# Pg13_FPGA_Connectors.net
KiCad netlist of a schematic drawn in Altium Designer
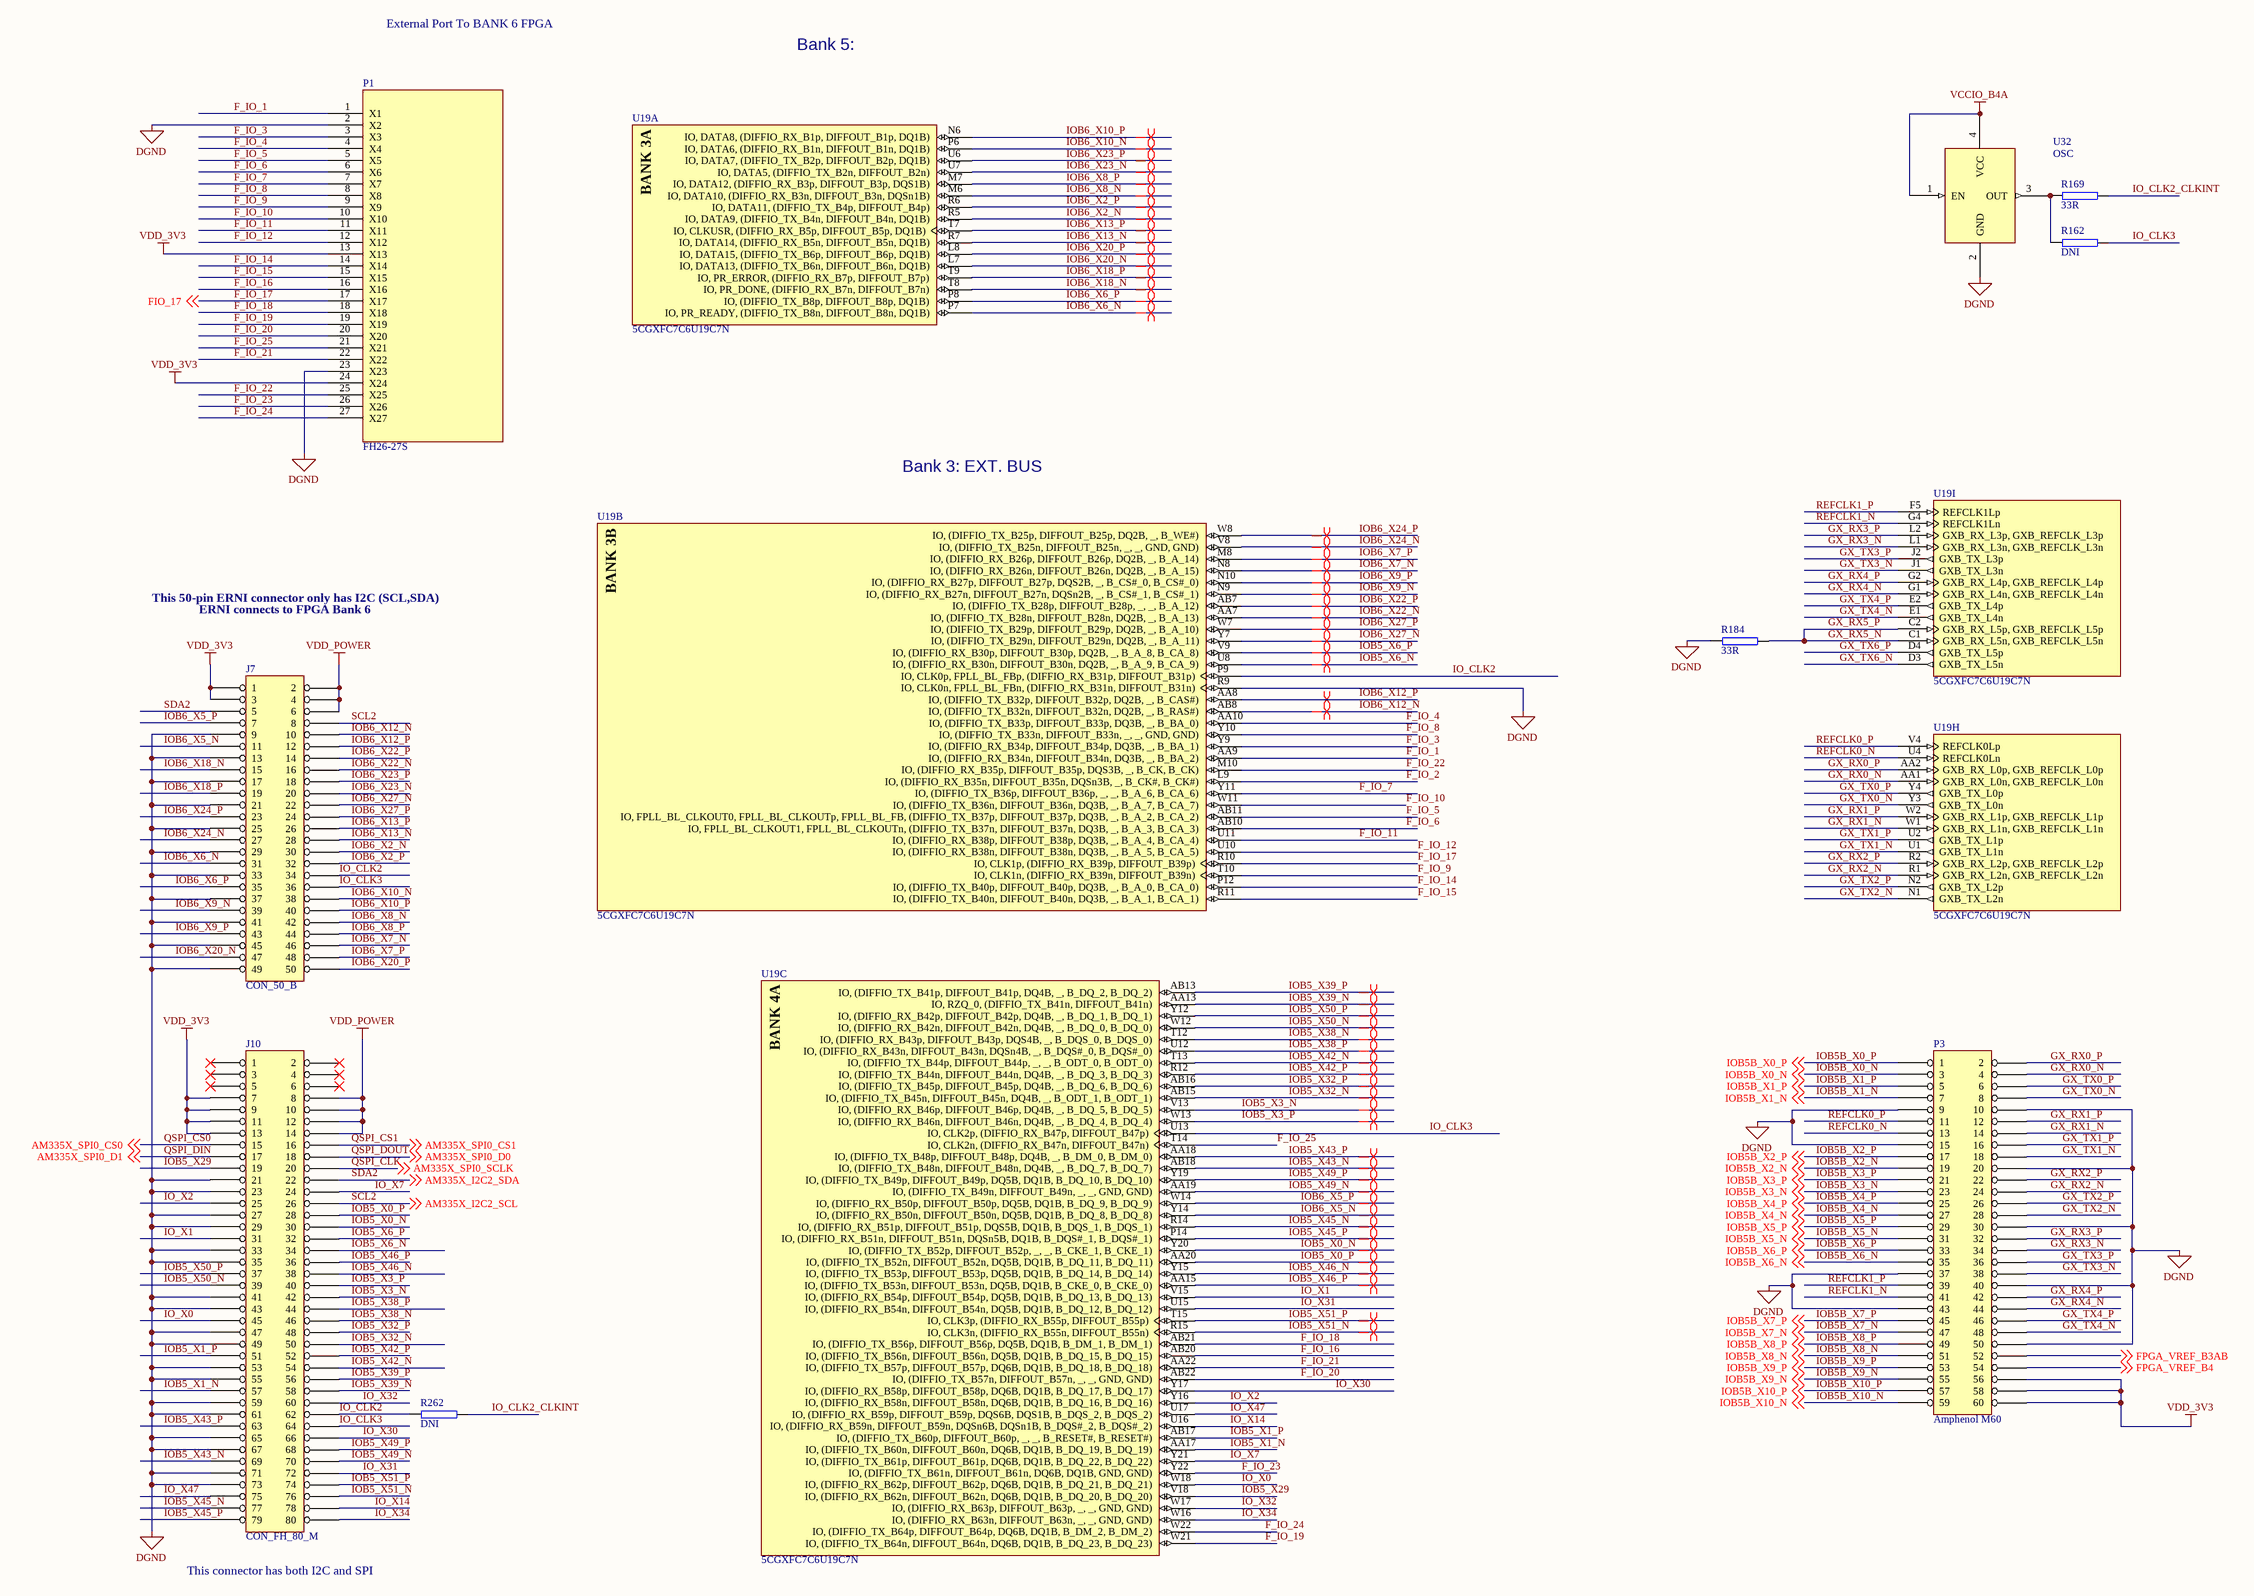
[diagram p0: Pg13_FPGA_Connectors.SchDoc]

(export (version "E")
  (design (tool "Eeschema 10.0.6"))
  (components
    (comp (ref "J7")
      (value "CON_50_B")
      (footprint "CON_50_B")
      (description "HEADER 25X2")
      (libsource (lib "Fireflash_B") (part "CON_50_B"))
    )
    (comp (ref "J10")
      (value "CON_FH_80_M")
      (footprint "CON_FH_80_M")
      (description "AMPHENOL FH")
      (libsource (lib "Fireflash_B") (part "CON_FH_80_M"))
    )
    (comp (ref "P1")
      (value "FH26-27S")
      (footprint "FH26-27S")
      (description "Flexible PCB connector")
      (libsource (lib "Fireflash_B") (part "FH26-27S"))
    )
    (comp (ref "P3")
      (value "Amphenol M60")
      (footprint "CON60_M")
      (description "Header vertical 60 M")
      (libsource (lib "AddtoMini_revC") (part "CON60_FH_M"))
    )
    (comp (ref "R162")
      (value "DNI")
      (footprint "sc0402")
      (description "Resistor")
      (libsource (lib "Ibis4") (part "RES"))
    )
    (comp (ref "R169")
      (value "33R")
      (footprint "sc0402")
      (description "Resistor")
      (libsource (lib "Ibis4") (part "RES"))
    )
    (comp (ref "R184")
      (value "33R")
      (footprint "sc0402")
      (description "Resistor")
      (libsource (lib "Ibis4") (part "RES"))
    )
    (comp (ref "R262")
      (value "DNI")
      (footprint "sc0402")
      (description "Resistor")
      (libsource (lib "Ibis4") (part "RES"))
    )
    (comp (ref "U19")
      (value "5CGXFC7C6U19C7N")
      (footprint "ALTR-UBGA484_A-190")
      (fields (field (name "MANUFACTURER") "Altera"))
      (libsource (lib "Altera Cyclone V") (part "5CGXFC7C6U19C7N"))
    )
    (comp (ref "U32")
      (value "OSC")
      (footprint "Osc 3.2x2.5")
      (description "XTAL OSCILLATOR MODULE")
      (libsource (lib "Fireflash_B") (part "OSC"))
    )
  )
  (nets
    (net (code "1") (name "/F_IO_1") (class "Default")
      (node (ref "P1") (pin "1") (pinfunction "X1_1") (pintype "passive"))
      (node (ref "U19") (pin "AA9") (pinfunction "IO,_(DIFFIO_RX_B34n,_DIFFOUT_B34n,_DQ3B,__,_B_BA_2)_AA9") (pintype "bidirectional"))
    )
    (net (code "2") (name "/F_IO_2") (class "Default")
      (node (ref "U19") (pin "L9") (pinfunction "IO,_(DIFFIO_RX_B35n,_DIFFOUT_B35n,_DQSn3B,__,_B_CK#,_B_CK#)_L9") (pintype "bidirectional"))
    )
    (net (code "3") (name "/F_IO_3") (class "Default")
      (node (ref "P1") (pin "3") (pinfunction "X3_3") (pintype "passive"))
      (node (ref "U19") (pin "Y9") (pinfunction "IO,_(DIFFIO_RX_B34p,_DIFFOUT_B34p,_DQ3B,__,_B_BA_1)_Y9") (pintype "bidirectional"))
    )
    (net (code "4") (name "/F_IO_4") (class "Default")
      (node (ref "P1") (pin "4") (pinfunction "X4_4") (pintype "passive"))
      (node (ref "U19") (pin "AA10") (pinfunction "IO,_(DIFFIO_TX_B33p,_DIFFOUT_B33p,_DQ3B,__,_B_BA_0)_AA10") (pintype "bidirectional"))
    )
    (net (code "5") (name "/F_IO_5") (class "Default")
      (node (ref "P1") (pin "5") (pinfunction "X5_5") (pintype "passive"))
      (node (ref "U19") (pin "AB11") (pinfunction "IO,_FPLL_BL_CLKOUT0,_FPLL_BL_CLKOUTp,_FPLL_BL_FB,_(DIFFIO_TX_B37p,_DIFFOUT_B37p,_DQ3B,__,_B_A_2,_B_CA_2)_AB11") (pintype "bidirectional"))
    )
    (net (code "6") (name "/F_IO_6") (class "Default")
      (node (ref "P1") (pin "6") (pinfunction "X6_6") (pintype "passive"))
      (node (ref "U19") (pin "AB10") (pinfunction "IO,_FPLL_BL_CLKOUT1,_FPLL_BL_CLKOUTn,_(DIFFIO_TX_B37n,_DIFFOUT_B37n,_DQ3B,__,_B_A_3,_B_CA_3)_AB10") (pintype "bidirectional"))
    )
    (net (code "7") (name "/F_IO_7") (class "Default")
      (node (ref "P1") (pin "7") (pinfunction "X7_7") (pintype "passive"))
      (node (ref "U19") (pin "Y11") (pinfunction "IO,_(DIFFIO_TX_B36p,_DIFFOUT_B36p,__,__,_B_A_6,_B_CA_6)_Y11") (pintype "bidirectional"))
    )
    (net (code "8") (name "/F_IO_8") (class "Default")
      (node (ref "P1") (pin "8") (pinfunction "X8_8") (pintype "passive"))
      (node (ref "U19") (pin "Y10") (pinfunction "IO,_(DIFFIO_TX_B33n,_DIFFOUT_B33n,__,__,_GND,_GND)_Y10") (pintype "bidirectional"))
    )
    (net (code "9") (name "/F_IO_9") (class "Default")
      (node (ref "P1") (pin "9") (pinfunction "X9_9") (pintype "passive"))
      (node (ref "U19") (pin "T10") (pinfunction "IO,_CLK1n,_(DIFFIO_RX_B39n,_DIFFOUT_B39n)_T10") (pintype "bidirectional"))
    )
    (net (code "10") (name "/F_IO_10") (class "Default")
      (node (ref "P1") (pin "10") (pinfunction "X10_10") (pintype "passive"))
      (node (ref "U19") (pin "W11") (pinfunction "IO,_(DIFFIO_TX_B36n,_DIFFOUT_B36n,_DQ3B,__,_B_A_7,_B_CA_7)_W11") (pintype "bidirectional"))
    )
    (net (code "11") (name "/F_IO_11") (class "Default")
      (node (ref "P1") (pin "11") (pinfunction "X11_11") (pintype "passive"))
      (node (ref "U19") (pin "U11") (pinfunction "IO,_(DIFFIO_RX_B38p,_DIFFOUT_B38p,_DQ3B,__,_B_A_4,_B_CA_4)_U11") (pintype "bidirectional"))
    )
    (net (code "12") (name "/F_IO_12") (class "Default")
      (node (ref "P1") (pin "12") (pinfunction "X12_12") (pintype "passive"))
      (node (ref "U19") (pin "U10") (pinfunction "IO,_(DIFFIO_RX_B38n,_DIFFOUT_B38n,_DQ3B,__,_B_A_5,_B_CA_5)_U10") (pintype "bidirectional"))
    )
    (net (code "13") (name "/F_IO_14") (class "Default")
      (node (ref "P1") (pin "14") (pinfunction "X14_14") (pintype "passive"))
      (node (ref "U19") (pin "P12") (pinfunction "IO,_(DIFFIO_TX_B40p,_DIFFOUT_B40p,_DQ3B,__,_B_A_0,_B_CA_0)_P12") (pintype "bidirectional"))
    )
    (net (code "14") (name "/F_IO_15") (class "Default")
      (node (ref "P1") (pin "15") (pinfunction "X15_15") (pintype "passive"))
      (node (ref "U19") (pin "R11") (pinfunction "IO,_(DIFFIO_TX_B40n,_DIFFOUT_B40n,_DQ3B,__,_B_A_1,_B_CA_1)_R11") (pintype "bidirectional"))
    )
    (net (code "15") (name "/F_IO_16") (class "Default")
      (node (ref "P1") (pin "16") (pinfunction "X16_16") (pintype "passive"))
      (node (ref "U19") (pin "AB20") (pinfunction "IO,_(DIFFIO_TX_B56n,_DIFFOUT_B56n,_DQ5B,_DQ1B,_B_DQ_15,_B_DQ_15)_AB20") (pintype "bidirectional"))
    )
    (net (code "16") (name "/F_IO_18") (class "Default")
      (node (ref "P1") (pin "18") (pinfunction "X18_18") (pintype "passive"))
      (node (ref "U19") (pin "AB21") (pinfunction "IO,_(DIFFIO_TX_B56p,_DIFFOUT_B56p,_DQ5B,_DQ1B,_B_DM_1,_B_DM_1)_AB21") (pintype "bidirectional"))
    )
    (net (code "17") (name "/F_IO_19") (class "Default")
      (node (ref "P1") (pin "19") (pinfunction "X19_19") (pintype "passive"))
      (node (ref "U19") (pin "W21") (pinfunction "IO,_(DIFFIO_TX_B64n,_DIFFOUT_B64n,_DQ6B,_DQ1B,_B_DQ_23,_B_DQ_23)_W21") (pintype "bidirectional"))
    )
    (net (code "18") (name "/F_IO_20") (class "Default")
      (node (ref "P1") (pin "20") (pinfunction "X20_20") (pintype "passive"))
      (node (ref "U19") (pin "AB22") (pinfunction "IO,_(DIFFIO_TX_B57n,_DIFFOUT_B57n,__,__,_GND,_GND)_AB22") (pintype "bidirectional"))
    )
    (net (code "19") (name "/F_IO_21") (class "Default")
      (node (ref "P1") (pin "22") (pinfunction "X22_22") (pintype "passive"))
      (node (ref "U19") (pin "AA22") (pinfunction "IO,_(DIFFIO_TX_B57p,_DIFFOUT_B57p,_DQ6B,_DQ1B,_B_DQ_18,_B_DQ_18)_AA22") (pintype "bidirectional"))
    )
    (net (code "20") (name "/F_IO_22") (class "Default")
      (node (ref "P1") (pin "25") (pinfunction "X25_25") (pintype "passive"))
      (node (ref "U19") (pin "M10") (pinfunction "IO,_(DIFFIO_RX_B35p,_DIFFOUT_B35p,_DQS3B,__,_B_CK,_B_CK)_M10") (pintype "bidirectional"))
    )
    (net (code "21") (name "/F_IO_23") (class "Default")
      (node (ref "P1") (pin "26") (pinfunction "X26_26") (pintype "passive"))
      (node (ref "U19") (pin "Y22") (pinfunction "IO,_(DIFFIO_TX_B61n,_DIFFOUT_B61n,_DQ6B,_DQ1B,_GND,_GND)_Y22") (pintype "bidirectional"))
    )
    (net (code "22") (name "/F_IO_24") (class "Default")
      (node (ref "P1") (pin "27") (pinfunction "X27_27") (pintype "passive"))
      (node (ref "U19") (pin "W22") (pinfunction "IO,_(DIFFIO_TX_B64p,_DIFFOUT_B64p,_DQ6B,_DQ1B,_B_DM_2,_B_DM_2)_W22") (pintype "bidirectional"))
    )
    (net (code "23") (name "/F_IO_25") (class "Default")
      (node (ref "P1") (pin "21") (pinfunction "X21_21") (pintype "passive"))
      (node (ref "U19") (pin "T14") (pinfunction "IO,_CLK2n,_(DIFFIO_RX_B47n,_DIFFOUT_B47n)_T14") (pintype "bidirectional"))
    )
    (net (code "24") (name "/GX_RX0_N") (class "Default")
      (node (ref "P3") (pin "4") (pinfunction "4_4") (pintype "passive"))
      (node (ref "U19") (pin "AA1") (pinfunction "GXB_RX_L0n,_GXB_REFCLK_L0n_AA1") (pintype "input"))
    )
    (net (code "25") (name "/GX_RX0_P") (class "Default")
      (node (ref "P3") (pin "2") (pinfunction "2_2") (pintype "passive"))
      (node (ref "U19") (pin "AA2") (pinfunction "GXB_RX_L0p,_GXB_REFCLK_L0p_AA2") (pintype "input"))
    )
    (net (code "26") (name "/GX_RX1_N") (class "Default")
      (node (ref "P3") (pin "14") (pinfunction "14_14") (pintype "passive"))
      (node (ref "U19") (pin "W1") (pinfunction "GXB_RX_L1n,_GXB_REFCLK_L1n_W1") (pintype "input"))
    )
    (net (code "27") (name "/GX_RX1_P") (class "Default")
      (node (ref "P3") (pin "12") (pinfunction "12_12") (pintype "passive"))
      (node (ref "U19") (pin "W2") (pinfunction "GXB_RX_L1p,_GXB_REFCLK_L1p_W2") (pintype "input"))
    )
    (net (code "28") (name "/GX_RX2_N") (class "Default")
      (node (ref "P3") (pin "24") (pinfunction "24_24") (pintype "passive"))
      (node (ref "U19") (pin "R1") (pinfunction "GXB_RX_L2n,_GXB_REFCLK_L2n_R1") (pintype "input"))
    )
    (net (code "29") (name "/GX_RX2_P") (class "Default")
      (node (ref "P3") (pin "22") (pinfunction "22_22") (pintype "passive"))
      (node (ref "U19") (pin "R2") (pinfunction "GXB_RX_L2p,_GXB_REFCLK_L2p_R2") (pintype "input"))
    )
    (net (code "30") (name "/GX_RX3_N") (class "Default")
      (node (ref "P3") (pin "34") (pinfunction "34_34") (pintype "passive"))
      (node (ref "U19") (pin "L1") (pinfunction "GXB_RX_L3n,_GXB_REFCLK_L3n_L1") (pintype "input"))
    )
    (net (code "31") (name "/GX_RX3_P") (class "Default")
      (node (ref "P3") (pin "32") (pinfunction "32_32") (pintype "passive"))
      (node (ref "U19") (pin "L2") (pinfunction "GXB_RX_L3p,_GXB_REFCLK_L3p_L2") (pintype "input"))
    )
    (net (code "32") (name "/GX_RX4_N") (class "Default")
      (node (ref "P3") (pin "44") (pinfunction "44_44") (pintype "passive"))
      (node (ref "U19") (pin "G1") (pinfunction "GXB_RX_L4n,_GXB_REFCLK_L4n_G1") (pintype "input"))
    )
    (net (code "33") (name "/GX_RX4_P") (class "Default")
      (node (ref "P3") (pin "42") (pinfunction "42_42") (pintype "passive"))
      (node (ref "U19") (pin "G2") (pinfunction "GXB_RX_L4p,_GXB_REFCLK_L4p_G2") (pintype "input"))
    )
    (net (code "34") (name "/GX_RX5_N") (class "Default")
      (node (ref "R184") (pin "2") (pintype "passive"))
      (node (ref "U19") (pin "C1") (pinfunction "GXB_RX_L5n,_GXB_REFCLK_L5n_C1") (pintype "input"))
      (node (ref "U19") (pin "C2") (pinfunction "GXB_RX_L5p,_GXB_REFCLK_L5p_C2") (pintype "input"))
    )
    (net (code "35") (name "/GX_TX0_N") (class "Default")
      (node (ref "P3") (pin "8") (pinfunction "8_8") (pintype "passive"))
      (node (ref "U19") (pin "Y3") (pinfunction "GXB_TX_L0n_Y3") (pintype "output"))
    )
    (net (code "36") (name "/GX_TX0_P") (class "Default")
      (node (ref "P3") (pin "6") (pinfunction "6_6") (pintype "passive"))
      (node (ref "U19") (pin "Y4") (pinfunction "GXB_TX_L0p_Y4") (pintype "output"))
    )
    (net (code "37") (name "/GX_TX1_N") (class "Default")
      (node (ref "P3") (pin "18") (pinfunction "18_18") (pintype "passive"))
      (node (ref "U19") (pin "U1") (pinfunction "GXB_TX_L1n_U1") (pintype "output"))
    )
    (net (code "38") (name "/GX_TX1_P") (class "Default")
      (node (ref "P3") (pin "16") (pinfunction "16_16") (pintype "passive"))
      (node (ref "U19") (pin "U2") (pinfunction "GXB_TX_L1p_U2") (pintype "output"))
    )
    (net (code "39") (name "/GX_TX2_N") (class "Default")
      (node (ref "P3") (pin "28") (pinfunction "28_28") (pintype "passive"))
      (node (ref "U19") (pin "N1") (pinfunction "GXB_TX_L2n_N1") (pintype "output"))
    )
    (net (code "40") (name "/GX_TX2_P") (class "Default")
      (node (ref "P3") (pin "26") (pinfunction "26_26") (pintype "passive"))
      (node (ref "U19") (pin "N2") (pinfunction "GXB_TX_L2p_N2") (pintype "output"))
    )
    (net (code "41") (name "/GX_TX3_N") (class "Default")
      (node (ref "P3") (pin "38") (pinfunction "38_38") (pintype "passive"))
      (node (ref "U19") (pin "J1") (pinfunction "GXB_TX_L3n_J1") (pintype "output"))
    )
    (net (code "42") (name "/GX_TX3_P") (class "Default")
      (node (ref "P3") (pin "36") (pinfunction "36_36") (pintype "passive"))
      (node (ref "U19") (pin "J2") (pinfunction "GXB_TX_L3p_J2") (pintype "output"))
    )
    (net (code "43") (name "/GX_TX4_N") (class "Default")
      (node (ref "P3") (pin "48") (pinfunction "48_48") (pintype "passive"))
      (node (ref "U19") (pin "E1") (pinfunction "GXB_TX_L4n_E1") (pintype "output"))
    )
    (net (code "44") (name "/GX_TX4_P") (class "Default")
      (node (ref "P3") (pin "46") (pinfunction "46_46") (pintype "passive"))
      (node (ref "U19") (pin "E2") (pinfunction "GXB_TX_L4p_E2") (pintype "output"))
    )
    (net (code "45") (name "/GX_TX6_N") (class "Default")
      (node (ref "U19") (pin "D3") (pinfunction "GXB_TX_L5n_D3") (pintype "output"))
    )
    (net (code "46") (name "/GX_TX6_P") (class "Default")
      (node (ref "U19") (pin "D4") (pinfunction "GXB_TX_L5p_D4") (pintype "output"))
    )
    (net (code "47") (name "/IOB5_X0_N") (class "Default")
      (node (ref "J10") (pin "30") (pinfunction "30_30") (pintype "passive"))
      (node (ref "U19") (pin "Y20") (pinfunction "IO,_(DIFFIO_TX_B52p,_DIFFOUT_B52p,__,__,_B_CKE_1,_B_CKE_1)_Y20") (pintype "bidirectional"))
    )
    (net (code "48") (name "/IOB5_X0_P") (class "Default")
      (node (ref "J10") (pin "28") (pinfunction "28_28") (pintype "passive"))
      (node (ref "U19") (pin "AA20") (pinfunction "IO,_(DIFFIO_TX_B52n,_DIFFOUT_B52n,_DQ5B,_DQ1B,_B_DQ_11,_B_DQ_11)_AA20") (pintype "bidirectional"))
    )
    (net (code "49") (name "/IOB5_X1_N") (class "Default")
      (node (ref "J10") (pin "57") (pinfunction "57_57") (pintype "passive"))
      (node (ref "U19") (pin "AA17") (pinfunction "IO,_(DIFFIO_TX_B60n,_DIFFOUT_B60n,_DQ6B,_DQ1B,_B_DQ_19,_B_DQ_19)_AA17") (pintype "bidirectional"))
    )
    (net (code "50") (name "/IOB5_X1_P") (class "Default")
      (node (ref "J10") (pin "51") (pinfunction "51_51") (pintype "passive"))
      (node (ref "U19") (pin "AB17") (pinfunction "IO,_(DIFFIO_TX_B60p,_DIFFOUT_B60p,__,__,_B_RESET#,_B_RESET#)_AB17") (pintype "bidirectional"))
    )
    (net (code "51") (name "/IOB5_X3_N") (class "Default")
      (node (ref "J10") (pin "42") (pinfunction "42_42") (pintype "passive"))
      (node (ref "U19") (pin "V13") (pinfunction "IO,_(DIFFIO_RX_B46p,_DIFFOUT_B46p,_DQ4B,__,_B_DQ_5,_B_DQ_5)_V13") (pintype "bidirectional"))
    )
    (net (code "52") (name "/IOB5_X3_P") (class "Default")
      (node (ref "J10") (pin "40") (pinfunction "40_40") (pintype "passive"))
      (node (ref "U19") (pin "W13") (pinfunction "IO,_(DIFFIO_RX_B46n,_DIFFOUT_B46n,_DQ4B,__,_B_DQ_4,_B_DQ_4)_W13") (pintype "bidirectional"))
    )
    (net (code "53") (name "/IOB5_X6_N") (class "Default")
      (node (ref "J10") (pin "34") (pinfunction "34_34") (pintype "passive"))
      (node (ref "U19") (pin "U8") (pinfunction "IO,_(DIFFIO_RX_B30n,_DIFFOUT_B30n,_DQ2B,__,_B_A_9,_B_CA_9)_U8") (pintype "bidirectional"))
    )
    (net (code "54") (name "/IOB5_X6_P") (class "Default")
      (node (ref "J10") (pin "32") (pinfunction "32_32") (pintype "passive"))
      (node (ref "U19") (pin "V9") (pinfunction "IO,_(DIFFIO_RX_B30p,_DIFFOUT_B30p,_DQ2B,__,_B_A_8,_B_CA_8)_V9") (pintype "bidirectional"))
    )
    (net (code "55") (name "/IOB5_X29") (class "Default")
      (node (ref "J10") (pin "19") (pinfunction "19_19") (pintype "passive"))
      (node (ref "U19") (pin "V18") (pinfunction "IO,_(DIFFIO_RX_B62n,_DIFFOUT_B62n,_DQ6B,_DQ1B,_B_DQ_20,_B_DQ_20)_V18") (pintype "bidirectional"))
    )
    (net (code "56") (name "/IOB5_X32_N") (class "Default")
      (node (ref "J10") (pin "50") (pinfunction "50_50") (pintype "passive"))
      (node (ref "U19") (pin "AB15") (pinfunction "IO,_(DIFFIO_TX_B45n,_DIFFOUT_B45n,_DQ4B,__,_B_ODT_1,_B_ODT_1)_AB15") (pintype "bidirectional"))
    )
    (net (code "57") (name "/IOB5_X32_P") (class "Default")
      (node (ref "J10") (pin "48") (pinfunction "48_48") (pintype "passive"))
      (node (ref "U19") (pin "AB16") (pinfunction "IO,_(DIFFIO_TX_B45p,_DIFFOUT_B45p,_DQ4B,__,_B_DQ_6,_B_DQ_6)_AB16") (pintype "bidirectional"))
    )
    (net (code "58") (name "/IOB5_X38_N") (class "Default")
      (node (ref "J10") (pin "46") (pinfunction "46_46") (pintype "passive"))
      (node (ref "U19") (pin "T12") (pinfunction "IO,_(DIFFIO_RX_B43p,_DIFFOUT_B43p,_DQS4B,__,_B_DQS_0,_B_DQS_0)_T12") (pintype "bidirectional"))
    )
    (net (code "59") (name "/IOB5_X38_P") (class "Default")
      (node (ref "J10") (pin "44") (pinfunction "44_44") (pintype "passive"))
      (node (ref "U19") (pin "U12") (pinfunction "IO,_(DIFFIO_RX_B43n,_DIFFOUT_B43n,_DQSn4B,__,_B_DQS#_0,_B_DQS#_0)_U12") (pintype "bidirectional"))
    )
    (net (code "60") (name "/IOB5_X39_N") (class "Default")
      (node (ref "J10") (pin "58") (pinfunction "58_58") (pintype "passive"))
      (node (ref "U19") (pin "AA13") (pinfunction "IO,_RZQ_0,_(DIFFIO_TX_B41n,_DIFFOUT_B41n)_AA13") (pintype "bidirectional"))
    )
    (net (code "61") (name "/IOB5_X39_P") (class "Default")
      (node (ref "J10") (pin "56") (pinfunction "56_56") (pintype "passive"))
      (node (ref "U19") (pin "AB13") (pinfunction "IO,_(DIFFIO_TX_B41p,_DIFFOUT_B41p,_DQ4B,__,_B_DQ_2,_B_DQ_2)_AB13") (pintype "bidirectional"))
    )
    (net (code "62") (name "/IOB5_X42_N") (class "Default")
      (node (ref "J10") (pin "54") (pinfunction "54_54") (pintype "passive"))
      (node (ref "U19") (pin "T13") (pinfunction "IO,_(DIFFIO_TX_B44p,_DIFFOUT_B44p,__,__,_B_ODT_0,_B_ODT_0)_T13") (pintype "bidirectional"))
    )
    (net (code "63") (name "/IOB5_X42_P") (class "Default")
      (node (ref "J10") (pin "52") (pinfunction "52_52") (pintype "passive"))
      (node (ref "U19") (pin "R12") (pinfunction "IO,_(DIFFIO_TX_B44n,_DIFFOUT_B44n,_DQ4B,__,_B_DQ_3,_B_DQ_3)_R12") (pintype "bidirectional"))
    )
    (net (code "64") (name "/IOB5_X43_N") (class "Default")
      (node (ref "J10") (pin "69") (pinfunction "69_69") (pintype "passive"))
      (node (ref "U19") (pin "AB18") (pinfunction "IO,_(DIFFIO_TX_B48n,_DIFFOUT_B48n,_DQ4B,__,_B_DQ_7,_B_DQ_7)_AB18") (pintype "bidirectional"))
    )
    (net (code "65") (name "/IOB5_X43_P") (class "Default")
      (node (ref "J10") (pin "63") (pinfunction "63_63") (pintype "passive"))
      (node (ref "U19") (pin "AA18") (pinfunction "IO,_(DIFFIO_TX_B48p,_DIFFOUT_B48p,_DQ4B,__,_B_DM_0,_B_DM_0)_AA18") (pintype "bidirectional"))
    )
    (net (code "66") (name "/IOB5_X45_N") (class "Default")
      (node (ref "J10") (pin "77") (pinfunction "77_77") (pintype "passive"))
      (node (ref "U19") (pin "R14") (pinfunction "IO,_(DIFFIO_RX_B51p,_DIFFOUT_B51p,_DQS5B,_DQ1B,_B_DQS_1,_B_DQS_1)_R14") (pintype "bidirectional"))
    )
    (net (code "67") (name "/IOB5_X45_P") (class "Default")
      (node (ref "J10") (pin "79") (pinfunction "79_79") (pintype "passive"))
      (node (ref "U19") (pin "P14") (pinfunction "IO,_(DIFFIO_RX_B51n,_DIFFOUT_B51n,_DQSn5B,_DQ1B,_B_DQS#_1,_B_DQS#_1)_P14") (pintype "bidirectional"))
    )
    (net (code "68") (name "/IOB5_X46_N") (class "Default")
      (node (ref "J10") (pin "38") (pinfunction "38_38") (pintype "passive"))
      (node (ref "U19") (pin "Y15") (pinfunction "IO,_(DIFFIO_TX_B53p,_DIFFOUT_B53p,_DQ5B,_DQ1B,_B_DQ_14,_B_DQ_14)_Y15") (pintype "bidirectional"))
    )
    (net (code "69") (name "/IOB5_X46_P") (class "Default")
      (node (ref "J10") (pin "36") (pinfunction "36_36") (pintype "passive"))
      (node (ref "U19") (pin "AA15") (pinfunction "IO,_(DIFFIO_TX_B53n,_DIFFOUT_B53n,_DQ5B,_DQ1B,_B_CKE_0,_B_CKE_0)_AA15") (pintype "bidirectional"))
    )
    (net (code "70") (name "/IOB5_X49_N") (class "Default")
      (node (ref "J10") (pin "70") (pinfunction "70_70") (pintype "passive"))
      (node (ref "U19") (pin "AA19") (pinfunction "IO,_(DIFFIO_TX_B49n,_DIFFOUT_B49n,__,__,_GND,_GND)_AA19") (pintype "bidirectional"))
    )
    (net (code "71") (name "/IOB5_X49_P") (class "Default")
      (node (ref "J10") (pin "68") (pinfunction "68_68") (pintype "passive"))
      (node (ref "U19") (pin "Y19") (pinfunction "IO,_(DIFFIO_TX_B49p,_DIFFOUT_B49p,_DQ5B,_DQ1B,_B_DQ_10,_B_DQ_10)_Y19") (pintype "bidirectional"))
    )
    (net (code "72") (name "/IOB5_X50_N") (class "Default")
      (node (ref "J10") (pin "39") (pinfunction "39_39") (pintype "passive"))
      (node (ref "U19") (pin "W12") (pinfunction "IO,_(DIFFIO_RX_B42n,_DIFFOUT_B42n,_DQ4B,__,_B_DQ_0,_B_DQ_0)_W12") (pintype "bidirectional"))
    )
    (net (code "73") (name "/IOB5_X50_P") (class "Default")
      (node (ref "J10") (pin "37") (pinfunction "37_37") (pintype "passive"))
      (node (ref "U19") (pin "Y12") (pinfunction "IO,_(DIFFIO_RX_B42p,_DIFFOUT_B42p,_DQ4B,__,_B_DQ_1,_B_DQ_1)_Y12") (pintype "bidirectional"))
    )
    (net (code "74") (name "/IOB5_X51_N") (class "Default")
      (node (ref "J10") (pin "76") (pinfunction "76_76") (pintype "passive"))
      (node (ref "U19") (pin "R15") (pinfunction "IO,_CLK3n,_(DIFFIO_RX_B55n,_DIFFOUT_B55n)_R15") (pintype "bidirectional"))
    )
    (net (code "75") (name "/IOB5_X51_P") (class "Default")
      (node (ref "J10") (pin "74") (pinfunction "74_74") (pintype "passive"))
      (node (ref "U19") (pin "T15") (pinfunction "IO,_CLK3p,_(DIFFIO_RX_B55p,_DIFFOUT_B55p)_T15") (pintype "bidirectional"))
    )
    (net (code "76") (name "/IOB6_X2_N") (class "Default")
      (node (ref "J7") (pin "30") (pinfunction "30_30") (pintype "passive"))
      (node (ref "U19") (pin "R5") (pinfunction "IO,_DATA9,_(DIFFIO_TX_B4n,_DIFFOUT_B4n,_DQ1B)_R5") (pintype "bidirectional"))
    )
    (net (code "77") (name "/IOB6_X2_P") (class "Default")
      (node (ref "J7") (pin "32") (pinfunction "32_32") (pintype "passive"))
      (node (ref "U19") (pin "R6") (pinfunction "IO,_DATA11,_(DIFFIO_TX_B4p,_DIFFOUT_B4p)_R6") (pintype "bidirectional"))
    )
    (net (code "78") (name "/IOB6_X5_N") (class "Default")
      (node (ref "J7") (pin "11") (pinfunction "11_11") (pintype "passive"))
      (node (ref "U19") (pin "Y14") (pinfunction "IO,_(DIFFIO_RX_B50n,_DIFFOUT_B50n,_DQ5B,_DQ1B,_B_DQ_8,_B_DQ_8)_Y14") (pintype "bidirectional"))
    )
    (net (code "79") (name "/IOB6_X5_P") (class "Default")
      (node (ref "J7") (pin "7") (pinfunction "7_7") (pintype "passive"))
      (node (ref "U19") (pin "W14") (pinfunction "IO,_(DIFFIO_RX_B50p,_DIFFOUT_B50p,_DQ5B,_DQ1B,_B_DQ_9,_B_DQ_9)_W14") (pintype "bidirectional"))
    )
    (net (code "80") (name "/IOB6_X6_N") (class "Default")
      (node (ref "J7") (pin "31") (pinfunction "31_31") (pintype "passive"))
      (node (ref "U19") (pin "P7") (pinfunction "IO,_PR_READY,_(DIFFIO_TX_B8n,_DIFFOUT_B8n,_DQ1B)_P7") (pintype "bidirectional"))
    )
    (net (code "81") (name "/IOB6_X6_P") (class "Default")
      (node (ref "J7") (pin "35") (pinfunction "35_35") (pintype "passive"))
      (node (ref "U19") (pin "P8") (pinfunction "IO,_(DIFFIO_TX_B8p,_DIFFOUT_B8p,_DQ1B)_P8") (pintype "bidirectional"))
    )
    (net (code "82") (name "/IOB6_X7_N") (class "Default")
      (node (ref "J7") (pin "46") (pinfunction "46_46") (pintype "passive"))
      (node (ref "U19") (pin "N8") (pinfunction "IO,_(DIFFIO_RX_B26n,_DIFFOUT_B26n,_DQ2B,__,_B_A_15)_N8") (pintype "bidirectional"))
    )
    (net (code "83") (name "/IOB6_X7_P") (class "Default")
      (node (ref "J7") (pin "48") (pinfunction "48_48") (pintype "passive"))
      (node (ref "U19") (pin "M8") (pinfunction "IO,_(DIFFIO_RX_B26p,_DIFFOUT_B26p,_DQ2B,__,_B_A_14)_M8") (pintype "bidirectional"))
    )
    (net (code "84") (name "/IOB6_X8_N") (class "Default")
      (node (ref "J7") (pin "42") (pinfunction "42_42") (pintype "passive"))
      (node (ref "U19") (pin "M6") (pinfunction "IO,_DATA10,_(DIFFIO_RX_B3n,_DIFFOUT_B3n,_DQSn1B)_M6") (pintype "bidirectional"))
    )
    (net (code "85") (name "/IOB6_X8_P") (class "Default")
      (node (ref "J7") (pin "44") (pinfunction "44_44") (pintype "passive"))
      (node (ref "U19") (pin "M7") (pinfunction "IO,_DATA12,_(DIFFIO_RX_B3p,_DIFFOUT_B3p,_DQS1B)_M7") (pintype "bidirectional"))
    )
    (net (code "86") (name "/IOB6_X9_N") (class "Default")
      (node (ref "J7") (pin "39") (pinfunction "39_39") (pintype "passive"))
      (node (ref "U19") (pin "N9") (pinfunction "IO,_(DIFFIO_RX_B27n,_DIFFOUT_B27n,_DQSn2B,__,_B_CS#_1,_B_CS#_1)_N9") (pintype "bidirectional"))
    )
    (net (code "87") (name "/IOB6_X9_P") (class "Default")
      (node (ref "J7") (pin "43") (pinfunction "43_43") (pintype "passive"))
      (node (ref "U19") (pin "N10") (pinfunction "IO,_(DIFFIO_RX_B27p,_DIFFOUT_B27p,_DQS2B,__,_B_CS#_0,_B_CS#_0)_N10") (pintype "bidirectional"))
    )
    (net (code "88") (name "/IOB6_X10_N") (class "Default")
      (node (ref "J7") (pin "38") (pinfunction "38_38") (pintype "passive"))
      (node (ref "U19") (pin "P6") (pinfunction "IO,_DATA6,_(DIFFIO_RX_B1n,_DIFFOUT_B1n,_DQ1B)_P6") (pintype "bidirectional"))
    )
    (net (code "89") (name "/IOB6_X10_P") (class "Default")
      (node (ref "J7") (pin "40") (pinfunction "40_40") (pintype "passive"))
      (node (ref "U19") (pin "N6") (pinfunction "IO,_DATA8,_(DIFFIO_RX_B1p,_DIFFOUT_B1p,_DQ1B)_N6") (pintype "bidirectional"))
    )
    (net (code "90") (name "/IOB6_X12_N") (class "Default")
      (node (ref "J7") (pin "10") (pinfunction "10_10") (pintype "passive"))
      (node (ref "U19") (pin "AB8") (pinfunction "IO,_(DIFFIO_TX_B32n,_DIFFOUT_B32n,_DQ2B,__,_B_RAS#)_AB8") (pintype "bidirectional"))
    )
    (net (code "91") (name "/IOB6_X12_P") (class "Default")
      (node (ref "J7") (pin "12") (pinfunction "12_12") (pintype "passive"))
      (node (ref "U19") (pin "AA8") (pinfunction "IO,_(DIFFIO_TX_B32p,_DIFFOUT_B32p,_DQ2B,__,_B_CAS#)_AA8") (pintype "bidirectional"))
    )
    (net (code "92") (name "/IOB6_X13_N") (class "Default")
      (node (ref "J7") (pin "28") (pinfunction "28_28") (pintype "passive"))
      (node (ref "U19") (pin "R7") (pinfunction "IO,_DATA14,_(DIFFIO_RX_B5n,_DIFFOUT_B5n,_DQ1B)_R7") (pintype "bidirectional"))
    )
    (net (code "93") (name "/IOB6_X13_P") (class "Default")
      (node (ref "J7") (pin "26") (pinfunction "26_26") (pintype "passive"))
      (node (ref "U19") (pin "T7") (pinfunction "IO,_CLKUSR,_(DIFFIO_RX_B5p,_DIFFOUT_B5p,_DQ1B)_T7") (pintype "bidirectional"))
    )
    (net (code "94") (name "/IOB6_X18_N") (class "Default")
      (node (ref "J7") (pin "15") (pinfunction "15_15") (pintype "passive"))
      (node (ref "U19") (pin "T8") (pinfunction "IO,_PR_DONE,_(DIFFIO_RX_B7n,_DIFFOUT_B7n)_T8") (pintype "bidirectional"))
    )
    (net (code "95") (name "/IOB6_X18_P") (class "Default")
      (node (ref "J7") (pin "19") (pinfunction "19_19") (pintype "passive"))
      (node (ref "U19") (pin "T9") (pinfunction "IO,_PR_ERROR,_(DIFFIO_RX_B7p,_DIFFOUT_B7p)_T9") (pintype "bidirectional"))
    )
    (net (code "96") (name "/IOB6_X20_N") (class "Default")
      (node (ref "J7") (pin "47") (pinfunction "47_47") (pintype "passive"))
      (node (ref "U19") (pin "L7") (pinfunction "IO,_DATA13,_(DIFFIO_TX_B6n,_DIFFOUT_B6n,_DQ1B)_L7") (pintype "bidirectional"))
    )
    (net (code "97") (name "/IOB6_X20_P") (class "Default")
      (node (ref "J7") (pin "50") (pinfunction "50_50") (pintype "passive"))
      (node (ref "U19") (pin "L8") (pinfunction "IO,_DATA15,_(DIFFIO_TX_B6p,_DIFFOUT_B6p,_DQ1B)_L8") (pintype "bidirectional"))
    )
    (net (code "98") (name "/IOB6_X22_N") (class "Default")
      (node (ref "J7") (pin "16") (pinfunction "16_16") (pintype "passive"))
      (node (ref "U19") (pin "AA7") (pinfunction "IO,_(DIFFIO_TX_B28n,_DIFFOUT_B28n,_DQ2B,__,_B_A_13)_AA7") (pintype "bidirectional"))
    )
    (net (code "99") (name "/IOB6_X22_P") (class "Default")
      (node (ref "J7") (pin "14") (pinfunction "14_14") (pintype "passive"))
      (node (ref "U19") (pin "AB7") (pinfunction "IO,_(DIFFIO_TX_B28p,_DIFFOUT_B28p,__,__,_B_A_12)_AB7") (pintype "bidirectional"))
    )
    (net (code "100") (name "/IOB6_X23_N") (class "Default")
      (node (ref "J7") (pin "20") (pinfunction "20_20") (pintype "passive"))
      (node (ref "U19") (pin "U7") (pinfunction "IO,_DATA5,_(DIFFIO_TX_B2n,_DIFFOUT_B2n)_U7") (pintype "bidirectional"))
    )
    (net (code "101") (name "/IOB6_X23_P") (class "Default")
      (node (ref "J7") (pin "18") (pinfunction "18_18") (pintype "passive"))
      (node (ref "U19") (pin "U6") (pinfunction "IO,_DATA7,_(DIFFIO_TX_B2p,_DIFFOUT_B2p,_DQ1B)_U6") (pintype "bidirectional"))
    )
    (net (code "102") (name "/IOB6_X24_N") (class "Default")
      (node (ref "J7") (pin "27") (pinfunction "27_27") (pintype "passive"))
      (node (ref "U19") (pin "V8") (pinfunction "IO,_(DIFFIO_TX_B25n,_DIFFOUT_B25n,__,__,_GND,_GND)_V8") (pintype "bidirectional"))
    )
    (net (code "103") (name "/IOB6_X24_P") (class "Default")
      (node (ref "J7") (pin "23") (pinfunction "23_23") (pintype "passive"))
      (node (ref "U19") (pin "W8") (pinfunction "IO,_(DIFFIO_TX_B25p,_DIFFOUT_B25p,_DQ2B,__,_B_WE#)_W8") (pintype "bidirectional"))
    )
    (net (code "104") (name "/IOB6_X27_N") (class "Default")
      (node (ref "J7") (pin "22") (pinfunction "22_22") (pintype "passive"))
      (node (ref "U19") (pin "Y7") (pinfunction "IO,_(DIFFIO_TX_B29n,_DIFFOUT_B29n,_DQ2B,__,_B_A_11)_Y7") (pintype "bidirectional"))
    )
    (net (code "105") (name "/IOB6_X27_P") (class "Default")
      (node (ref "J7") (pin "24") (pinfunction "24_24") (pintype "passive"))
      (node (ref "U19") (pin "W7") (pinfunction "IO,_(DIFFIO_TX_B29p,_DIFFOUT_B29p,_DQ2B,__,_B_A_10)_W7") (pintype "bidirectional"))
    )
    (net (code "106") (name "/IO_CLK2") (class "Default")
      (node (ref "J10") (pin "62") (pinfunction "62_62") (pintype "passive"))
      (node (ref "J7") (pin "34") (pinfunction "34_34") (pintype "passive"))
      (node (ref "R262") (pin "1") (pintype "passive"))
      (node (ref "U19") (pin "P9") (pinfunction "IO,_CLK0p,_FPLL_BL_FBp,_(DIFFIO_RX_B31p,_DIFFOUT_B31p)_P9") (pintype "bidirectional"))
    )
    (net (code "107") (name "/IO_CLK2_CLKINT") (class "Default")
      (node (ref "R169") (pin "2") (pintype "passive"))
      (node (ref "R262") (pin "2") (pintype "passive"))
    )
    (net (code "108") (name "/IO_CLK3") (class "Default")
      (node (ref "J10") (pin "64") (pinfunction "64_64") (pintype "passive"))
      (node (ref "J7") (pin "36") (pinfunction "36_36") (pintype "passive"))
      (node (ref "R162") (pin "2") (pintype "passive"))
      (node (ref "U19") (pin "U13") (pinfunction "IO,_CLK2p,_(DIFFIO_RX_B47p,_DIFFOUT_B47p)_U13") (pintype "bidirectional"))
    )
    (net (code "109") (name "/IO_X0") (class "Default")
      (node (ref "J10") (pin "45") (pinfunction "45_45") (pintype "passive"))
      (node (ref "U19") (pin "W18") (pinfunction "IO,_(DIFFIO_RX_B62p,_DIFFOUT_B62p,_DQ6B,_DQ1B,_B_DQ_21,_B_DQ_21)_W18") (pintype "bidirectional"))
    )
    (net (code "110") (name "/IO_X1") (class "Default")
      (node (ref "J10") (pin "31") (pinfunction "31_31") (pintype "passive"))
      (node (ref "U19") (pin "V15") (pinfunction "IO,_(DIFFIO_RX_B54p,_DIFFOUT_B54p,_DQ5B,_DQ1B,_B_DQ_13,_B_DQ_13)_V15") (pintype "bidirectional"))
    )
    (net (code "111") (name "/IO_X2") (class "Default")
      (node (ref "J10") (pin "25") (pinfunction "25_25") (pintype "passive"))
      (node (ref "U19") (pin "Y16") (pinfunction "IO,_(DIFFIO_RX_B58n,_DIFFOUT_B58n,_DQ6B,_DQ1B,_B_DQ_16,_B_DQ_16)_Y16") (pintype "bidirectional"))
    )
    (net (code "112") (name "/IO_X7") (class "Default")
      (node (ref "J10") (pin "24") (pinfunction "24_24") (pintype "passive"))
      (node (ref "U19") (pin "Y21") (pinfunction "IO,_(DIFFIO_TX_B61p,_DIFFOUT_B61p,_DQ6B,_DQ1B,_B_DQ_22,_B_DQ_22)_Y21") (pintype "bidirectional"))
    )
    (net (code "113") (name "/IO_X14") (class "Default")
      (node (ref "J10") (pin "78") (pinfunction "78_78") (pintype "passive"))
      (node (ref "U19") (pin "U16") (pinfunction "IO,_(DIFFIO_RX_B59n,_DIFFOUT_B59n,_DQSn6B,_DQSn1B,_B_DQS#_2,_B_DQS#_2)_U16") (pintype "bidirectional"))
    )
    (net (code "114") (name "/IO_X30") (class "Default")
      (node (ref "J10") (pin "66") (pinfunction "66_66") (pintype "passive"))
      (node (ref "U19") (pin "Y17") (pinfunction "IO,_(DIFFIO_RX_B58p,_DIFFOUT_B58p,_DQ6B,_DQ1B,_B_DQ_17,_B_DQ_17)_Y17") (pintype "bidirectional"))
    )
    (net (code "115") (name "/IO_X31") (class "Default")
      (node (ref "J10") (pin "72") (pinfunction "72_72") (pintype "passive"))
      (node (ref "U19") (pin "U15") (pinfunction "IO,_(DIFFIO_RX_B54n,_DIFFOUT_B54n,_DQ5B,_DQ1B,_B_DQ_12,_B_DQ_12)_U15") (pintype "bidirectional"))
    )
    (net (code "116") (name "/IO_X32") (class "Default")
      (node (ref "J10") (pin "60") (pinfunction "60_60") (pintype "passive"))
      (node (ref "U19") (pin "W17") (pinfunction "IO,_(DIFFIO_RX_B63p,_DIFFOUT_B63p,__,__,_GND,_GND)_W17") (pintype "bidirectional"))
    )
    (net (code "117") (name "/IO_X34") (class "Default")
      (node (ref "J10") (pin "80") (pinfunction "80_80") (pintype "passive"))
      (node (ref "U19") (pin "W16") (pinfunction "IO,_(DIFFIO_RX_B63n,_DIFFOUT_B63n,__,__,_GND,_GND)_W16") (pintype "bidirectional"))
    )
    (net (code "118") (name "/IO_X47") (class "Default")
      (node (ref "J10") (pin "75") (pinfunction "75_75") (pintype "passive"))
      (node (ref "U19") (pin "U17") (pinfunction "IO,_(DIFFIO_RX_B59p,_DIFFOUT_B59p,_DQS6B,_DQS1B,_B_DQS_2,_B_DQS_2)_U17") (pintype "bidirectional"))
    )
    (net (code "119") (name "/REFCLK0_N") (class "Default")
      (node (ref "P3") (pin "13") (pinfunction "13_13") (pintype "passive"))
      (node (ref "U19") (pin "U4") (pinfunction "REFCLK0Ln_U4") (pintype "input"))
    )
    (net (code "120") (name "/REFCLK0_P") (class "Default")
      (node (ref "P3") (pin "11") (pinfunction "11_11") (pintype "passive"))
      (node (ref "U19") (pin "V4") (pinfunction "REFCLK0Lp_V4") (pintype "input"))
    )
    (net (code "121") (name "/REFCLK1_N") (class "Default")
      (node (ref "P3") (pin "41") (pinfunction "41_41") (pintype "passive"))
      (node (ref "U19") (pin "G4") (pinfunction "REFCLK1Ln_G4") (pintype "input"))
    )
    (net (code "122") (name "/REFCLK1_P") (class "Default")
      (node (ref "P3") (pin "39") (pinfunction "39_39") (pintype "passive"))
      (node (ref "U19") (pin "F5") (pinfunction "REFCLK1Lp_F5") (pintype "input"))
    )
    (net (code "123") (name "AM335X_I2C2_SCL") (class "Default")
      (node (ref "J10") (pin "26") (pinfunction "26_26") (pintype "passive"))
      (node (ref "J7") (pin "8") (pinfunction "8_8") (pintype "passive"))
    )
    (net (code "124") (name "AM335X_I2C2_SDA") (class "Default")
      (node (ref "J10") (pin "22") (pinfunction "22_22") (pintype "passive"))
      (node (ref "J7") (pin "5") (pinfunction "5_5") (pintype "passive"))
    )
    (net (code "125") (name "AM335X_SPI0_CS0") (class "Default")
      (node (ref "J10") (pin "15") (pinfunction "15_15") (pintype "passive"))
    )
    (net (code "126") (name "AM335X_SPI0_CS1") (class "Default")
      (node (ref "J10") (pin "16") (pinfunction "16_16") (pintype "passive"))
    )
    (net (code "127") (name "AM335X_SPI0_D0") (class "Default")
      (node (ref "J10") (pin "18") (pinfunction "18_18") (pintype "passive"))
    )
    (net (code "128") (name "AM335X_SPI0_D1") (class "Default")
      (node (ref "J10") (pin "17") (pinfunction "17_17") (pintype "passive"))
    )
    (net (code "129") (name "AM335X_SPI0_SCLK") (class "Default")
      (node (ref "J10") (pin "20") (pinfunction "20_20") (pintype "passive"))
    )
    (net (code "130") (name "DGND") (class "Default")
      (node (ref "J10") (pin "21") (pinfunction "21_21") (pintype "passive"))
      (node (ref "J10") (pin "23") (pinfunction "23_23") (pintype "passive"))
      (node (ref "J10") (pin "27") (pinfunction "27_27") (pintype "passive"))
      (node (ref "J10") (pin "29") (pinfunction "29_29") (pintype "passive"))
      (node (ref "J10") (pin "33") (pinfunction "33_33") (pintype "passive"))
      (node (ref "J10") (pin "35") (pinfunction "35_35") (pintype "passive"))
      (node (ref "J10") (pin "41") (pinfunction "41_41") (pintype "passive"))
      (node (ref "J10") (pin "43") (pinfunction "43_43") (pintype "passive"))
      (node (ref "J10") (pin "47") (pinfunction "47_47") (pintype "passive"))
      (node (ref "J10") (pin "49") (pinfunction "49_49") (pintype "passive"))
      (node (ref "J10") (pin "53") (pinfunction "53_53") (pintype "passive"))
      (node (ref "J10") (pin "55") (pinfunction "55_55") (pintype "passive"))
      (node (ref "J10") (pin "59") (pinfunction "59_59") (pintype "passive"))
      (node (ref "J10") (pin "61") (pinfunction "61_61") (pintype "passive"))
      (node (ref "J10") (pin "65") (pinfunction "65_65") (pintype "passive"))
      (node (ref "J10") (pin "67") (pinfunction "67_67") (pintype "passive"))
      (node (ref "J10") (pin "71") (pinfunction "71_71") (pintype "passive"))
      (node (ref "J10") (pin "73") (pinfunction "73_73") (pintype "passive"))
      (node (ref "J7") (pin "13") (pinfunction "13_13") (pintype "passive"))
      (node (ref "J7") (pin "17") (pinfunction "17_17") (pintype "passive"))
      (node (ref "J7") (pin "21") (pinfunction "21_21") (pintype "passive"))
      (node (ref "J7") (pin "25") (pinfunction "25_25") (pintype "passive"))
      (node (ref "J7") (pin "29") (pinfunction "29_29") (pintype "passive"))
      (node (ref "J7") (pin "33") (pinfunction "33_33") (pintype "passive"))
      (node (ref "J7") (pin "37") (pinfunction "37_37") (pintype "passive"))
      (node (ref "J7") (pin "41") (pinfunction "41_41") (pintype "passive"))
      (node (ref "J7") (pin "45") (pinfunction "45_45") (pintype "passive"))
      (node (ref "J7") (pin "49") (pinfunction "49_49") (pintype "passive"))
      (node (ref "J7") (pin "9") (pinfunction "9_9") (pintype "passive"))
      (node (ref "P1") (pin "2") (pinfunction "X2_2") (pintype "passive"))
      (node (ref "P1") (pin "23") (pinfunction "X23_23") (pintype "passive"))
      (node (ref "P3") (pin "10") (pinfunction "10_10") (pintype "passive"))
      (node (ref "P3") (pin "15") (pinfunction "15_15") (pintype "passive"))
      (node (ref "P3") (pin "20") (pinfunction "20_20") (pintype "passive"))
      (node (ref "P3") (pin "30") (pinfunction "30_30") (pintype "passive"))
      (node (ref "P3") (pin "37") (pinfunction "37_37") (pintype "passive"))
      (node (ref "P3") (pin "40") (pinfunction "40_40") (pintype "passive"))
      (node (ref "P3") (pin "43") (pinfunction "43_43") (pintype "passive"))
      (node (ref "P3") (pin "50") (pinfunction "50_50") (pintype "passive"))
      (node (ref "P3") (pin "9") (pinfunction "9_9") (pintype "passive"))
      (node (ref "R184") (pin "1") (pintype "passive"))
      (node (ref "U19") (pin "R9") (pinfunction "IO,_CLK0n,_FPLL_BL_FBn,_(DIFFIO_RX_B31n,_DIFFOUT_B31n)_R9") (pintype "bidirectional"))
      (node (ref "U32") (pin "2") (pinfunction "GND_2") (pintype "power_in"))
    )
    (net (code "131") (name "FIO_17") (class "Default")
      (node (ref "P1") (pin "17") (pinfunction "X17_17") (pintype "passive"))
      (node (ref "U19") (pin "R10") (pinfunction "IO,_CLK1p,_(DIFFIO_RX_B39p,_DIFFOUT_B39p)_R10") (pintype "bidirectional"))
    )
    (net (code "132") (name "FPGA_VREF_B3AB") (class "Default")
      (node (ref "P3") (pin "52") (pinfunction "52_52") (pintype "passive"))
    )
    (net (code "133") (name "FPGA_VREF_B4") (class "Default")
      (node (ref "P3") (pin "54") (pinfunction "54_54") (pintype "passive"))
    )
    (net (code "134") (name "IOB5B_X0_N") (class "Default")
      (node (ref "P3") (pin "3") (pinfunction "3_3") (pintype "passive"))
    )
    (net (code "135") (name "IOB5B_X0_P") (class "Default")
      (node (ref "P3") (pin "1") (pinfunction "1_1") (pintype "passive"))
    )
    (net (code "136") (name "IOB5B_X1_N") (class "Default")
      (node (ref "P3") (pin "7") (pinfunction "7_7") (pintype "passive"))
    )
    (net (code "137") (name "IOB5B_X1_P") (class "Default")
      (node (ref "P3") (pin "5") (pinfunction "5_5") (pintype "passive"))
    )
    (net (code "138") (name "IOB5B_X2_N") (class "Default")
      (node (ref "P3") (pin "19") (pinfunction "19_19") (pintype "passive"))
    )
    (net (code "139") (name "IOB5B_X2_P") (class "Default")
      (node (ref "P3") (pin "17") (pinfunction "17_17") (pintype "passive"))
    )
    (net (code "140") (name "IOB5B_X3_N") (class "Default")
      (node (ref "P3") (pin "23") (pinfunction "23_23") (pintype "passive"))
    )
    (net (code "141") (name "IOB5B_X3_P") (class "Default")
      (node (ref "P3") (pin "21") (pinfunction "21_21") (pintype "passive"))
    )
    (net (code "142") (name "IOB5B_X4_N") (class "Default")
      (node (ref "P3") (pin "27") (pinfunction "27_27") (pintype "passive"))
    )
    (net (code "143") (name "IOB5B_X4_P") (class "Default")
      (node (ref "P3") (pin "25") (pinfunction "25_25") (pintype "passive"))
    )
    (net (code "144") (name "IOB5B_X5_N") (class "Default")
      (node (ref "P3") (pin "31") (pinfunction "31_31") (pintype "passive"))
    )
    (net (code "145") (name "IOB5B_X5_P") (class "Default")
      (node (ref "P3") (pin "29") (pinfunction "29_29") (pintype "passive"))
    )
    (net (code "146") (name "IOB5B_X6_N") (class "Default")
      (node (ref "P3") (pin "35") (pinfunction "35_35") (pintype "passive"))
    )
    (net (code "147") (name "IOB5B_X6_P") (class "Default")
      (node (ref "P3") (pin "33") (pinfunction "33_33") (pintype "passive"))
    )
    (net (code "148") (name "IOB5B_X7_N") (class "Default")
      (node (ref "P3") (pin "47") (pinfunction "47_47") (pintype "passive"))
    )
    (net (code "149") (name "IOB5B_X7_P") (class "Default")
      (node (ref "P3") (pin "45") (pinfunction "45_45") (pintype "passive"))
    )
    (net (code "150") (name "IOB5B_X8_N") (class "Default")
      (node (ref "P3") (pin "51") (pinfunction "51_51") (pintype "passive"))
    )
    (net (code "151") (name "IOB5B_X8_P") (class "Default")
      (node (ref "P3") (pin "49") (pinfunction "49_49") (pintype "passive"))
    )
    (net (code "152") (name "IOB5B_X9_N") (class "Default")
      (node (ref "P3") (pin "55") (pinfunction "55_55") (pintype "passive"))
    )
    (net (code "153") (name "IOB5B_X9_P") (class "Default")
      (node (ref "P3") (pin "53") (pinfunction "53_53") (pintype "passive"))
    )
    (net (code "154") (name "IOB5B_X10_N") (class "Default")
      (node (ref "P3") (pin "59") (pinfunction "59_59") (pintype "passive"))
    )
    (net (code "155") (name "IOB5B_X10_P") (class "Default")
      (node (ref "P3") (pin "57") (pinfunction "57_57") (pintype "passive"))
    )
    (net (code "156") (name "Net-(U32-OUT)") (class "Default")
      (node (ref "R162") (pin "1") (pintype "passive"))
      (node (ref "R169") (pin "1") (pintype "passive"))
      (node (ref "U32") (pin "3") (pinfunction "OUT_3") (pintype "output"))
    )
    (net (code "157") (name "VCCIO_B4A") (class "Default")
      (node (ref "U32") (pin "1") (pinfunction "EN_1") (pintype "input"))
      (node (ref "U32") (pin "4") (pinfunction "VCC_4") (pintype "power_in"))
    )
    (net (code "158") (name "VDD_3V3") (class "Default")
      (node (ref "J10") (pin "11") (pinfunction "11_11") (pintype "passive"))
      (node (ref "J10") (pin "13") (pinfunction "13_13") (pintype "passive"))
      (node (ref "J10") (pin "7") (pinfunction "7_7") (pintype "passive"))
      (node (ref "J10") (pin "9") (pinfunction "9_9") (pintype "passive"))
      (node (ref "J7") (pin "1") (pinfunction "1_1") (pintype "passive"))
      (node (ref "J7") (pin "3") (pinfunction "3_3") (pintype "passive"))
      (node (ref "P1") (pin "13") (pinfunction "X13_13") (pintype "passive"))
      (node (ref "P1") (pin "24") (pinfunction "X24_24") (pintype "passive"))
      (node (ref "P3") (pin "56") (pinfunction "56_56") (pintype "passive"))
      (node (ref "P3") (pin "58") (pinfunction "58_58") (pintype "passive"))
      (node (ref "P3") (pin "60") (pinfunction "60_60") (pintype "passive"))
    )
    (net (code "159") (name "VDD_POWER") (class "Default")
      (node (ref "J10") (pin "10") (pinfunction "10_10") (pintype "passive"))
      (node (ref "J10") (pin "12") (pinfunction "12_12") (pintype "passive"))
      (node (ref "J10") (pin "14") (pinfunction "14_14") (pintype "passive"))
      (node (ref "J10") (pin "8") (pinfunction "8_8") (pintype "passive"))
      (node (ref "J7") (pin "2") (pinfunction "2_2") (pintype "passive"))
      (node (ref "J7") (pin "4") (pinfunction "4_4") (pintype "passive"))
      (node (ref "J7") (pin "6") (pinfunction "6_6") (pintype "passive"))
    )
    (net (code "160") (name "unconnected-(J10-Pad1)") (class "Default")
      (node (ref "J10") (pin "1") (pinfunction "1_1") (pintype "passive+no_connect"))
    )
    (net (code "161") (name "unconnected-(J10-Pad2)") (class "Default")
      (node (ref "J10") (pin "2") (pinfunction "2_2") (pintype "passive+no_connect"))
    )
    (net (code "162") (name "unconnected-(J10-Pad3)") (class "Default")
      (node (ref "J10") (pin "3") (pinfunction "3_3") (pintype "passive+no_connect"))
    )
    (net (code "163") (name "unconnected-(J10-Pad4)") (class "Default")
      (node (ref "J10") (pin "4") (pinfunction "4_4") (pintype "passive+no_connect"))
    )
    (net (code "164") (name "unconnected-(J10-Pad5)") (class "Default")
      (node (ref "J10") (pin "5") (pinfunction "5_5") (pintype "passive+no_connect"))
    )
    (net (code "165") (name "unconnected-(J10-Pad6)") (class "Default")
      (node (ref "J10") (pin "6") (pinfunction "6_6") (pintype "passive+no_connect"))
    )
  )
)
